# 2_Connection.net
KiCad netlist of a schematic drawn in Altium Designer
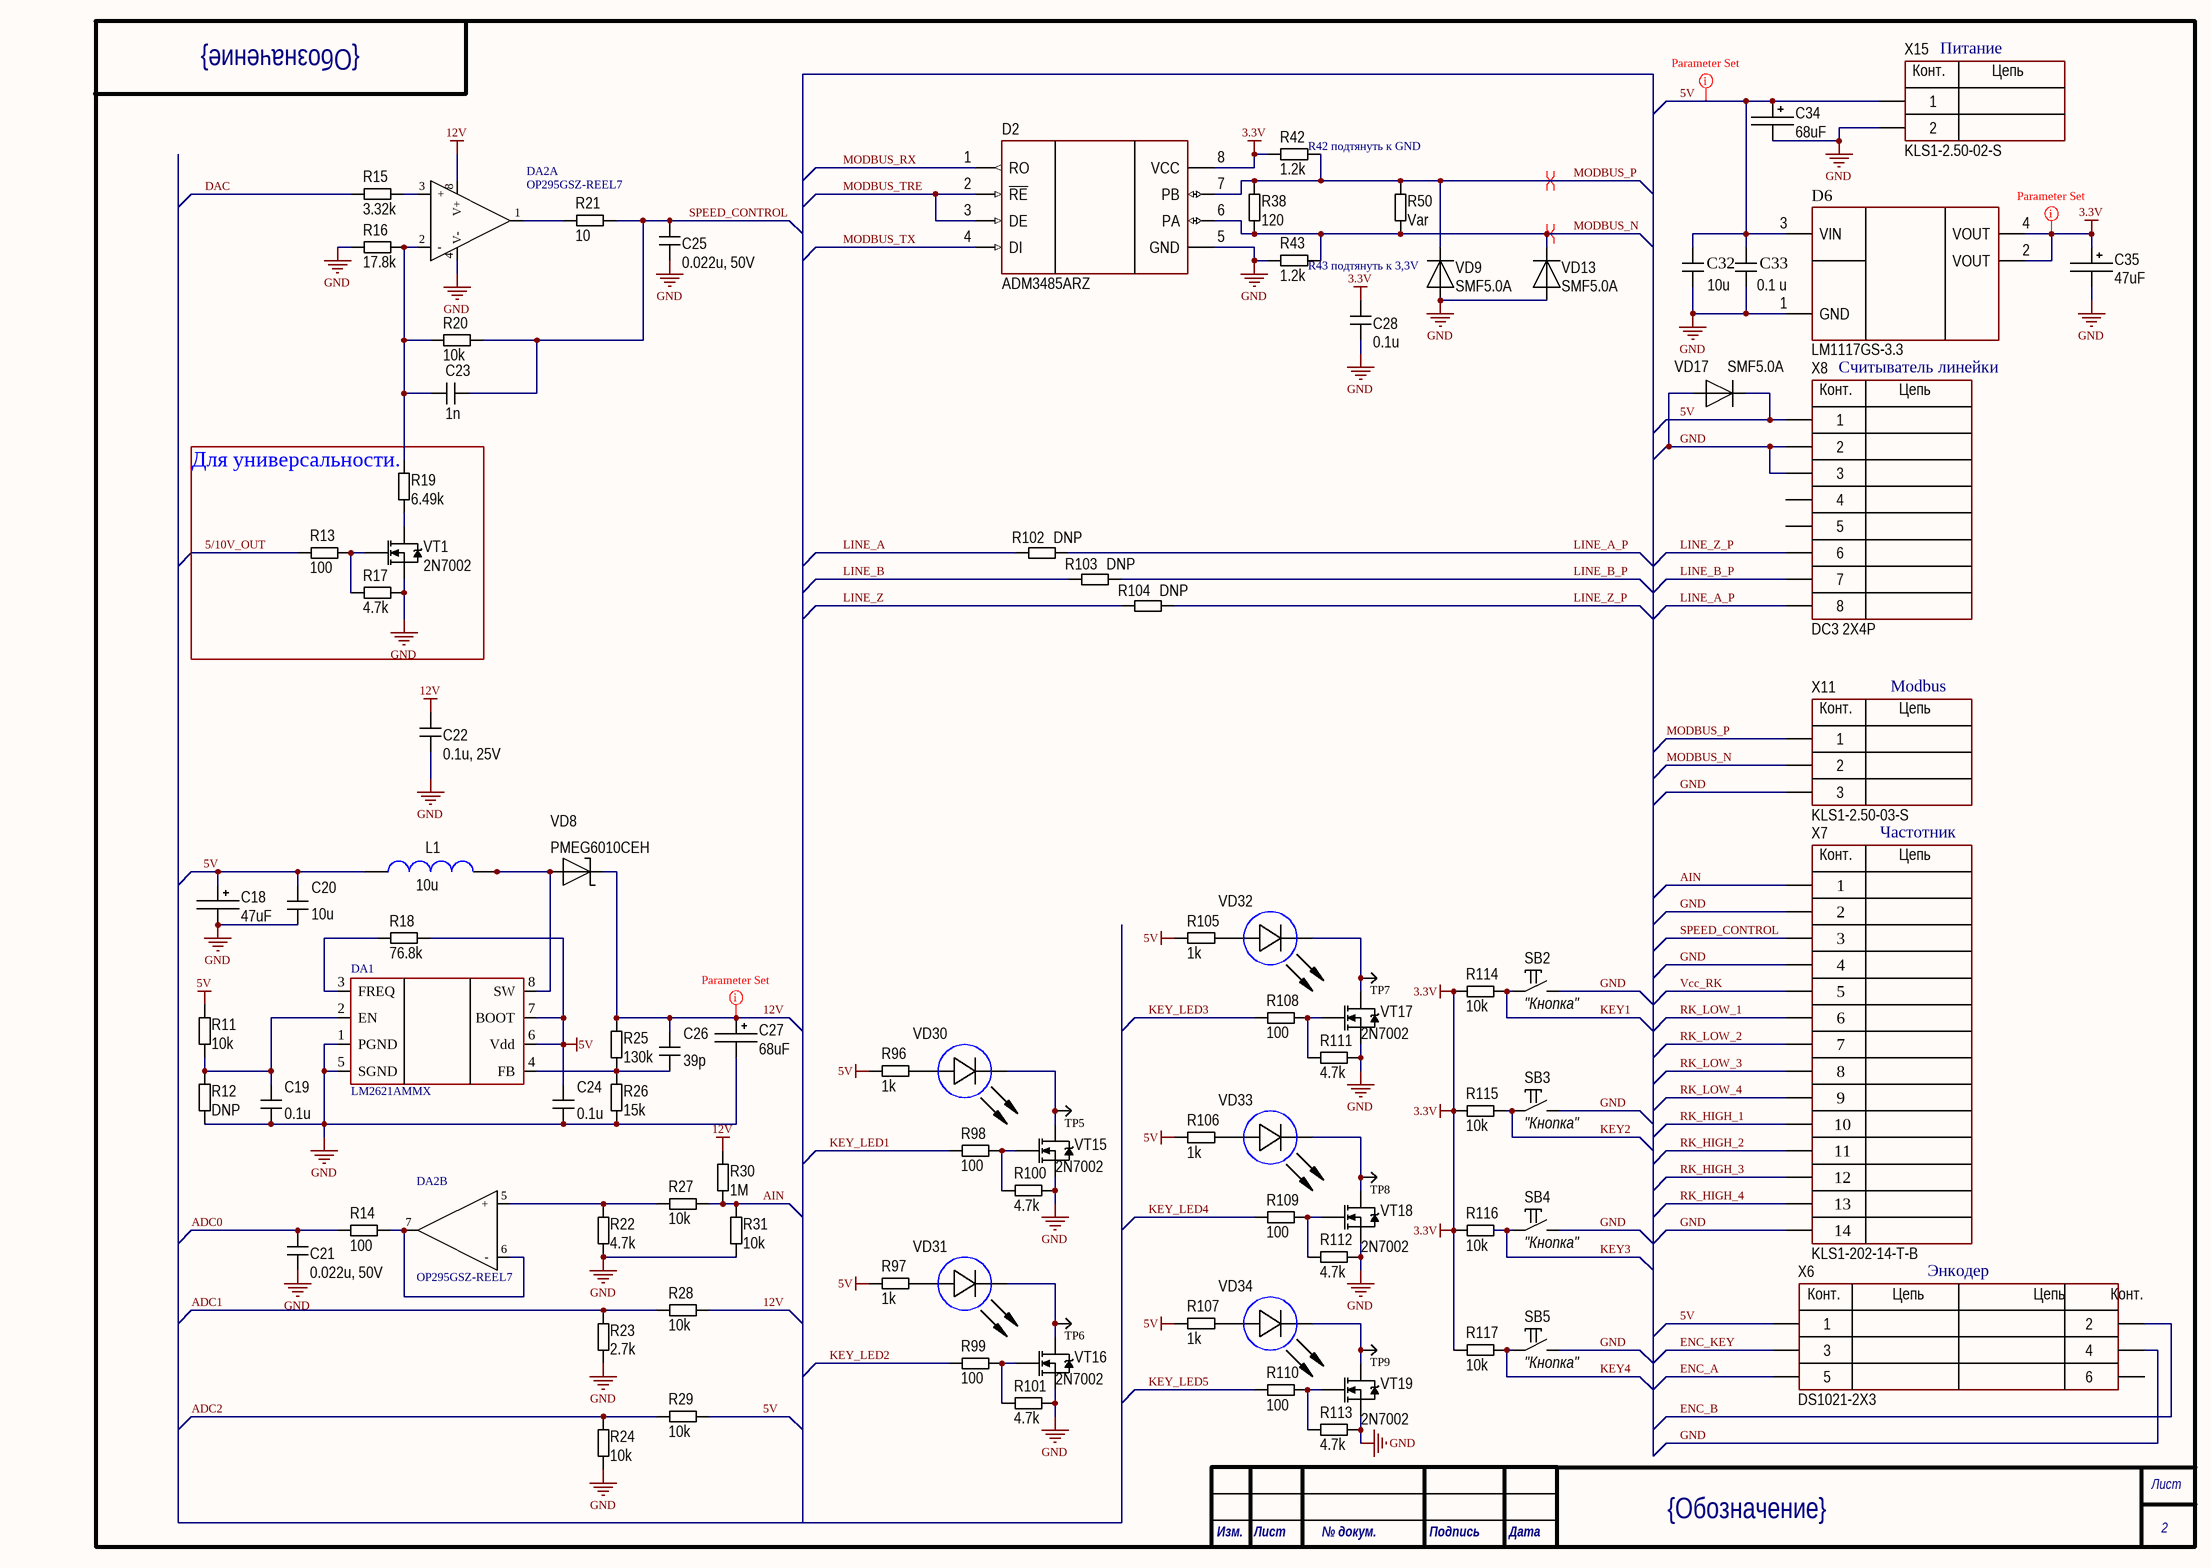
[diagram p0: 2_Connection.SchDoc]

(export (version "E")
  (design (tool "Eeschema 10.0.6"))
  (components
    (comp (ref "C18")
      (value "47uF")
      (footprint "TANTAL_B")
      (libsource (lib "Condensators") (part "TantalCap"))
    )
    (comp (ref "C19")
      (value "0.1u")
      (footprint "CH0603C")
      (libsource (lib "Condensators") (part "Capacitor"))
    )
    (comp (ref "C20") (value "10u") (footprint "CH0603C") (libsource (lib "Condensators") (part "Capacitor")))
    (comp (ref "C21")
      (value "0.022u, 50V")
      (footprint "CH0603C")
      (libsource (lib "Condensators") (part "Capacitor"))
    )
    (comp (ref "C22")
      (value "0.1u, 25V")
      (footprint "CH0603C")
      (libsource (lib "Condensators") (part "Capacitor"))
    )
    (comp (ref "C23") (value "1n") (footprint "CH0603C") (libsource (lib "Condensators") (part "Capacitor")))
    (comp (ref "C24")
      (value "0.1u")
      (footprint "CH0603C")
      (libsource (lib "Condensators") (part "Capacitor"))
    )
    (comp (ref "C25")
      (value "0.022u, 50V")
      (footprint "CH0603C")
      (libsource (lib "Condensators") (part "Capacitor"))
    )
    (comp (ref "C26") (value "39p") (footprint "CH0603C") (libsource (lib "Condensators") (part "Capacitor")))
    (comp (ref "C27")
      (value "68uF")
      (footprint "TANTAL_D")
      (libsource (lib "Condensators") (part "TantalCap"))
    )
    (comp (ref "C28")
      (value "0.1u")
      (footprint "CH0603C")
      (libsource (lib "Condensators") (part "Capacitor"))
    )
    (comp (ref "C32") (value "10u") (footprint "CH0805C") (libsource (lib "Condensators") (part "Capacitor")))
    (comp (ref "C33")
      (value "0.1 u")
      (footprint "CH0603C")
      (libsource (lib "Condensators") (part "Capacitor"))
    )
    (comp (ref "C34")
      (value "68uF")
      (footprint "TANTAL_B")
      (libsource (lib "Condensators") (part "TantalCap"))
    )
    (comp (ref "C35")
      (value "47uF")
      (footprint "TANTAL_A")
      (libsource (lib "Condensators") (part "TantalCap"))
    )
    (comp (ref "D2")
      (value "ADM3485ARZ")
      (footprint "8-SOIC")
      (description "RS485")
      (fields (field (name "MANUFACTURER") "Analog Devices Inc."))
      (libsource (lib "MicroIC") (part "ADM3485ARZ"))
    )
    (comp (ref "D6")
      (value "LM1117GS-3.3")
      (footprint "SOT223")
      (description "LDO")
      (fields (field (name "MANUFACTURER") "STMicroelectronics"))
      (libsource (lib "MicroIC") (part "LDL1117S33R"))
    )
    (comp (ref "DA1")
      (value "LM2621AMMX")
      (footprint "standard:8-SSOP")
      (libsource (lib "KSP_SchLib") (part "LM2623AMMX"))
    )
    (comp (ref "DA2")
      (value "OP295GSZ-REEL7")
      (footprint "standard:8-SOIC")
      (libsource (lib "KSP_SchLib") (part "OP295"))
    )
    (comp (ref "L1")
      (value "10u")
      (footprint "IND: IHLP2020")
      (libsource (lib "Inductance") (part "Inductor"))
    )
    (comp (ref "R11") (value "10k") (footprint "CH0603R") (libsource (lib "Resistors") (part "Resistor")))
    (comp (ref "R12") (value "DNP") (footprint "CH0603R") (libsource (lib "Resistors") (part "Resistor")))
    (comp (ref "R13") (value "100") (footprint "CH0603R") (libsource (lib "Resistors") (part "Resistor")))
    (comp (ref "R14") (value "100") (footprint "CH0603R") (libsource (lib "Resistors") (part "Resistor")))
    (comp (ref "R15") (value "3.32k") (footprint "CH0603R") (libsource (lib "Resistors") (part "Resistor")))
    (comp (ref "R16") (value "17.8k") (footprint "CH0603R") (libsource (lib "Resistors") (part "Resistor")))
    (comp (ref "R17") (value "4.7k") (footprint "CH0603R") (libsource (lib "Resistors") (part "Resistor")))
    (comp (ref "R18") (value "76.8k") (footprint "CH0603R") (libsource (lib "Resistors") (part "Resistor")))
    (comp (ref "R19") (value "6.49k") (footprint "CH0603R") (libsource (lib "Resistors") (part "Resistor")))
    (comp (ref "R20") (value "10k") (footprint "CH0603R") (libsource (lib "Resistors") (part "Resistor")))
    (comp (ref "R21") (value "10") (footprint "CH0603R") (libsource (lib "Resistors") (part "Resistor")))
    (comp (ref "R22") (value "4.7k") (footprint "CH0603R") (libsource (lib "Resistors") (part "Resistor")))
    (comp (ref "R23") (value "2.7k") (footprint "CH0603R") (libsource (lib "Resistors") (part "Resistor")))
    (comp (ref "R24") (value "10k") (footprint "CH0603R") (libsource (lib "Resistors") (part "Resistor")))
    (comp (ref "R25") (value "130k") (footprint "CH0603R") (libsource (lib "Resistors") (part "Resistor")))
    (comp (ref "R26") (value "15k") (footprint "CH0603R") (libsource (lib "Resistors") (part "Resistor")))
    (comp (ref "R27") (value "10k") (footprint "CH0603R") (libsource (lib "Resistors") (part "Resistor")))
    (comp (ref "R28") (value "10k") (footprint "CH0603R") (libsource (lib "Resistors") (part "Resistor")))
    (comp (ref "R29") (value "10k") (footprint "CH0603R") (libsource (lib "Resistors") (part "Resistor")))
    (comp (ref "R30") (value "1M") (footprint "CH0603R") (libsource (lib "Resistors") (part "Resistor")))
    (comp (ref "R31") (value "10k") (footprint "CH0603R") (libsource (lib "Resistors") (part "Resistor")))
    (comp (ref "R38") (value "120") (footprint "CH1206R") (libsource (lib "Resistors") (part "Resistor")))
    (comp (ref "R42") (value "1.2k") (footprint "CH0603R") (libsource (lib "Resistors") (part "Resistor")))
    (comp (ref "R43") (value "1.2k") (footprint "CH0603R") (libsource (lib "Resistors") (part "Resistor")))
    (comp (ref "R50")
      (value "Var")
      (footprint "CH1206R")
      (fields (field (name "PART") "JMV0805S5R6T661"))
      (libsource (lib "Resistors") (part "Resistor"))
    )
    (comp (ref "R96") (value "1k") (footprint "CH0805R") (libsource (lib "Resistors") (part "Resistor")))
    (comp (ref "R97") (value "1k") (footprint "CH0805R") (libsource (lib "Resistors") (part "Resistor")))
    (comp (ref "R98") (value "100") (footprint "CH0603R") (libsource (lib "Resistors") (part "Resistor")))
    (comp (ref "R99") (value "100") (footprint "CH0603R") (libsource (lib "Resistors") (part "Resistor")))
    (comp (ref "R100") (value "4.7k") (footprint "CH0603R") (libsource (lib "Resistors") (part "Resistor")))
    (comp (ref "R101") (value "4.7k") (footprint "CH0603R") (libsource (lib "Resistors") (part "Resistor")))
    (comp (ref "R102") (value "DNP") (footprint "CH0603R") (libsource (lib "Resistors") (part "Resistor")))
    (comp (ref "R103") (value "DNP") (footprint "CH0603R") (libsource (lib "Resistors") (part "Resistor")))
    (comp (ref "R104") (value "DNP") (footprint "CH0603R") (libsource (lib "Resistors") (part "Resistor")))
    (comp (ref "R105") (value "1k") (footprint "CH0805R") (libsource (lib "Resistors") (part "Resistor")))
    (comp (ref "R106") (value "1k") (footprint "CH0805R") (libsource (lib "Resistors") (part "Resistor")))
    (comp (ref "R107") (value "1k") (footprint "CH0805R") (libsource (lib "Resistors") (part "Resistor")))
    (comp (ref "R108") (value "100") (footprint "CH0603R") (libsource (lib "Resistors") (part "Resistor")))
    (comp (ref "R109") (value "100") (footprint "CH0603R") (libsource (lib "Resistors") (part "Resistor")))
    (comp (ref "R110") (value "100") (footprint "CH0603R") (libsource (lib "Resistors") (part "Resistor")))
    (comp (ref "R111") (value "4.7k") (footprint "CH0603R") (libsource (lib "Resistors") (part "Resistor")))
    (comp (ref "R112") (value "4.7k") (footprint "CH0603R") (libsource (lib "Resistors") (part "Resistor")))
    (comp (ref "R113") (value "4.7k") (footprint "CH0603R") (libsource (lib "Resistors") (part "Resistor")))
    (comp (ref "R114") (value "10k") (footprint "CH0603R") (libsource (lib "Resistors") (part "Resistor")))
    (comp (ref "R115") (value "10k") (footprint "CH0603R") (libsource (lib "Resistors") (part "Resistor")))
    (comp (ref "R116") (value "10k") (footprint "CH0603R") (libsource (lib "Resistors") (part "Resistor")))
    (comp (ref "R117") (value "10k") (footprint "CH0603R") (libsource (lib "Resistors") (part "Resistor")))
    (comp (ref "SB2")
      (value "\"Кнопка\"")
      (footprint "BUT: SKQGADE010")
      (description "6x6 mm")
      (libsource (lib "Connectors") (part "Tactile switches"))
    )
    (comp (ref "SB3")
      (value "\"Кнопка\"")
      (footprint "BUT: SKQGADE010")
      (description "6x6 mm")
      (libsource (lib "Connectors") (part "Tactile switches"))
    )
    (comp (ref "SB4")
      (value "\"Кнопка\"")
      (footprint "BUT: SKQGADE010")
      (description "6x6 mm")
      (libsource (lib "Connectors") (part "Tactile switches"))
    )
    (comp (ref "SB5")
      (value "\"Кнопка\"")
      (footprint "BUT: SKQGADE010")
      (description "6x6 mm")
      (libsource (lib "Connectors") (part "Tactile switches"))
    )
    (comp (ref "TP5") (value "~") (footprint "TestPoint") (libsource (lib "Melochi") (part "TestPoint")))
    (comp (ref "TP6") (value "~") (footprint "TestPoint") (libsource (lib "Melochi") (part "TestPoint")))
    (comp (ref "TP7") (value "~") (footprint "TestPoint") (libsource (lib "Melochi") (part "TestPoint")))
    (comp (ref "TP8") (value "~") (footprint "TestPoint") (libsource (lib "Melochi") (part "TestPoint")))
    (comp (ref "TP9") (value "~") (footprint "TestPoint") (libsource (lib "Melochi") (part "TestPoint")))
    (comp (ref "VD8")
      (value "PMEG6010CEH")
      (footprint "SOD123F")
      (libsource (lib "Diods") (part "Diod Schottky"))
    )
    (comp (ref "VD9")
      (value "SMF5.0A")
      (footprint "SOD123F")
      (fields (field (name "PART NUM") "SMAF5.0A"))
      (libsource (lib "Diods") (part "Diod"))
    )
    (comp (ref "VD13")
      (value "SMF5.0A")
      (footprint "SOD123F")
      (fields (field (name "PART NUM") "SMAF5.0A"))
      (libsource (lib "Diods") (part "Diod"))
    )
    (comp (ref "VD17")
      (value "SMF5.0A")
      (footprint "SOD123F")
      (fields (field (name "PART NUM") "SMAF5.0A"))
      (libsource (lib "Diods") (part "Diod"))
    )
    (comp (ref "VD30") (value "BLUE") (footprint "CH0603LB") (libsource (lib "Diods") (part "LED_1")))
    (comp (ref "VD31") (value "BLUE") (footprint "CH0603LB") (libsource (lib "Diods") (part "LED_1")))
    (comp (ref "VD32") (value "BLUE") (footprint "CH0603LB") (libsource (lib "Diods") (part "LED_1")))
    (comp (ref "VD33") (value "BLUE") (footprint "CH0603LB") (libsource (lib "Diods") (part "LED_1")))
    (comp (ref "VD34") (value "BLUE") (footprint "CH0603LB") (libsource (lib "Diods") (part "LED_1")))
    (comp (ref "VT1")
      (value "2N7002")
      (footprint "SOT23_123")
      (description "Mosfet")
      (libsource (lib "Tranzistor") (part "N-chanel"))
    )
    (comp (ref "VT15")
      (value "2N7002")
      (footprint "SOT23_123")
      (description "Mosfet")
      (libsource (lib "Tranzistor") (part "N-chanel"))
    )
    (comp (ref "VT16")
      (value "2N7002")
      (footprint "SOT23_123")
      (description "Mosfet")
      (libsource (lib "Tranzistor") (part "N-chanel"))
    )
    (comp (ref "VT17")
      (value "2N7002")
      (footprint "SOT23_123")
      (description "Mosfet")
      (libsource (lib "Tranzistor") (part "N-chanel"))
    )
    (comp (ref "VT18")
      (value "2N7002")
      (footprint "SOT23_123")
      (description "Mosfet")
      (libsource (lib "Tranzistor") (part "N-chanel"))
    )
    (comp (ref "VT19")
      (value "2N7002")
      (footprint "SOT23_123")
      (description "Mosfet")
      (libsource (lib "Tranzistor") (part "N-chanel"))
    )
    (comp (ref "X6")
      (value "DS1021-2X3")
      (footprint "CON: PLD-6 (without body)")
      (libsource (lib "Connectors") (part "6(2)-Connector"))
    )
    (comp (ref "X7")
      (value "KLS1-202-14-T-B")
      (footprint "CON: IDC-14MS")
      (libsource (lib "Connectors") (part "14-Connector"))
    )
    (comp (ref "X8")
      (value "DC3 2X4P")
      (footprint "CON: DC3 2x4P")
      (libsource (lib "Connectors") (part "8-Connector"))
    )
    (comp (ref "X11")
      (value "KLS1-2.50-03-S")
      (footprint "CON: CWF-3")
      (libsource (lib "Connectors") (part "3-Connector"))
    )
    (comp (ref "X15")
      (value "KLS1-2.50-02-S")
      (footprint "CON: CWF-2")
      (libsource (lib "Connectors") (part "2-Connector"))
    )
  )
  (nets
    (net (code "1") (name "/5{slash}10V_OUT") (class "Default")
      (node (ref "R13") (pin "2") (pinfunction "2_2") (pintype "passive"))
    )
    (net (code "2") (name "/ADC0") (class "Default")
      (node (ref "C21") (pin "2") (pinfunction "2_2") (pintype "passive"))
      (node (ref "R14") (pin "1") (pinfunction "1_1") (pintype "passive"))
    )
    (net (code "3") (name "/ADC1") (class "Default")
      (node (ref "R23") (pin "1") (pinfunction "1_1") (pintype "passive"))
      (node (ref "R28") (pin "2") (pinfunction "2_2") (pintype "passive"))
    )
    (net (code "4") (name "/ADC2") (class "Default")
      (node (ref "R24") (pin "1") (pinfunction "1_1") (pintype "passive"))
      (node (ref "R29") (pin "2") (pinfunction "2_2") (pintype "passive"))
    )
    (net (code "5") (name "/AIN") (class "Default")
      (node (ref "R27") (pin "1") (pinfunction "1_1") (pintype "passive"))
      (node (ref "R30") (pin "2") (pinfunction "2_2") (pintype "passive"))
      (node (ref "R31") (pin "1") (pinfunction "1_1") (pintype "passive"))
      (node (ref "X7") (pin "1") (pinfunction "1_1") (pintype "passive"))
    )
    (net (code "6") (name "/DAC") (class "Default")
      (node (ref "R15") (pin "2") (pinfunction "2_2") (pintype "passive"))
    )
    (net (code "7") (name "/ENC_A") (class "Default")
      (node (ref "X6") (pin "5") (pinfunction "5_5") (pintype "passive"))
    )
    (net (code "8") (name "/ENC_B") (class "Default")
      (node (ref "X6") (pin "2") (pinfunction "2_2") (pintype "passive"))
    )
    (net (code "9") (name "/ENC_KEY") (class "Default")
      (node (ref "X6") (pin "3") (pinfunction "3_3") (pintype "passive"))
    )
    (net (code "10") (name "/KEY1") (class "Default")
      (node (ref "R114") (pin "1") (pinfunction "1_1") (pintype "passive"))
      (node (ref "SB2") (pin "1") (pinfunction "1_1") (pintype "passive"))
    )
    (net (code "11") (name "/KEY2") (class "Default")
      (node (ref "R115") (pin "1") (pinfunction "1_1") (pintype "passive"))
      (node (ref "SB3") (pin "1") (pinfunction "1_1") (pintype "passive"))
    )
    (net (code "12") (name "/KEY3") (class "Default")
      (node (ref "R116") (pin "1") (pinfunction "1_1") (pintype "passive"))
      (node (ref "SB4") (pin "1") (pinfunction "1_1") (pintype "passive"))
    )
    (net (code "13") (name "/KEY4") (class "Default")
      (node (ref "R117") (pin "1") (pinfunction "1_1") (pintype "passive"))
      (node (ref "SB5") (pin "1") (pinfunction "1_1") (pintype "passive"))
    )
    (net (code "14") (name "/KEY_LED1") (class "Default")
      (node (ref "R98") (pin "2") (pinfunction "2_2") (pintype "passive"))
    )
    (net (code "15") (name "/KEY_LED2") (class "Default")
      (node (ref "R99") (pin "2") (pinfunction "2_2") (pintype "passive"))
    )
    (net (code "16") (name "/KEY_LED3") (class "Default")
      (node (ref "R108") (pin "2") (pinfunction "2_2") (pintype "passive"))
    )
    (net (code "17") (name "/KEY_LED4") (class "Default")
      (node (ref "R109") (pin "2") (pinfunction "2_2") (pintype "passive"))
    )
    (net (code "18") (name "/KEY_LED5") (class "Default")
      (node (ref "R110") (pin "2") (pinfunction "2_2") (pintype "passive"))
    )
    (net (code "19") (name "/LINE_A") (class "Default")
      (node (ref "R102") (pin "2") (pinfunction "2_2") (pintype "passive"))
    )
    (net (code "20") (name "/LINE_A_P") (class "Default")
      (node (ref "R102") (pin "1") (pinfunction "1_1") (pintype "passive"))
      (node (ref "X8") (pin "8") (pinfunction "8_8") (pintype "power_in"))
    )
    (net (code "21") (name "/LINE_B") (class "Default")
      (node (ref "R103") (pin "2") (pinfunction "2_2") (pintype "passive"))
    )
    (net (code "22") (name "/LINE_B_P") (class "Default")
      (node (ref "R103") (pin "1") (pinfunction "1_1") (pintype "passive"))
      (node (ref "X8") (pin "7") (pinfunction "7_7") (pintype "power_in"))
    )
    (net (code "23") (name "/LINE_Z") (class "Default")
      (node (ref "R104") (pin "2") (pinfunction "2_2") (pintype "passive"))
    )
    (net (code "24") (name "/LINE_Z_P") (class "Default")
      (node (ref "R104") (pin "1") (pinfunction "1_1") (pintype "passive"))
      (node (ref "X8") (pin "6") (pinfunction "6_6") (pintype "power_in"))
    )
    (net (code "25") (name "/MODBUS_N") (class "Default")
      (node (ref "D2") (pin "6") (pinfunction "PA_6") (pintype "bidirectional"))
      (node (ref "R38") (pin "1") (pinfunction "1_1") (pintype "passive"))
      (node (ref "R43") (pin "1") (pinfunction "1_1") (pintype "passive"))
      (node (ref "R50") (pin "1") (pinfunction "1_1") (pintype "passive"))
      (node (ref "VD13") (pin "2") (pinfunction "2_2") (pintype "passive"))
      (node (ref "X11") (pin "2") (pinfunction "2_2") (pintype "passive"))
    )
    (net (code "26") (name "/MODBUS_P") (class "Default")
      (node (ref "D2") (pin "7") (pinfunction "PB_7") (pintype "bidirectional"))
      (node (ref "R38") (pin "2") (pinfunction "2_2") (pintype "passive"))
      (node (ref "R42") (pin "1") (pinfunction "1_1") (pintype "passive"))
      (node (ref "R50") (pin "2") (pinfunction "2_2") (pintype "passive"))
      (node (ref "VD9") (pin "2") (pinfunction "2_2") (pintype "passive"))
      (node (ref "X11") (pin "1") (pinfunction "1_1") (pintype "passive"))
    )
    (net (code "27") (name "/MODBUS_RX") (class "Default")
      (node (ref "D2") (pin "1") (pinfunction "RO_1") (pintype "output"))
    )
    (net (code "28") (name "/MODBUS_TRE") (class "Default")
      (node (ref "D2") (pin "2") (pinfunction "~{RE}_2") (pintype "input"))
      (node (ref "D2") (pin "3") (pinfunction "DE_3") (pintype "input"))
    )
    (net (code "29") (name "/MODBUS_TX") (class "Default")
      (node (ref "D2") (pin "4") (pinfunction "DI_4") (pintype "input"))
    )
    (net (code "30") (name "/RK_HIGH_1") (class "Default")
      (node (ref "X7") (pin "10") (pinfunction "10_10") (pintype "power_in"))
    )
    (net (code "31") (name "/RK_HIGH_2") (class "Default")
      (node (ref "X7") (pin "11") (pinfunction "11_11") (pintype "power_in"))
    )
    (net (code "32") (name "/RK_HIGH_3") (class "Default")
      (node (ref "X7") (pin "12") (pinfunction "12_12") (pintype "power_in"))
    )
    (net (code "33") (name "/RK_HIGH_4") (class "Default")
      (node (ref "X7") (pin "13") (pinfunction "13_13") (pintype "power_in"))
    )
    (net (code "34") (name "/RK_LOW_1") (class "Default")
      (node (ref "X7") (pin "6") (pinfunction "6_6") (pintype "power_in"))
    )
    (net (code "35") (name "/RK_LOW_2") (class "Default")
      (node (ref "X7") (pin "7") (pinfunction "7_7") (pintype "power_in"))
    )
    (net (code "36") (name "/RK_LOW_3") (class "Default")
      (node (ref "X7") (pin "8") (pinfunction "8_8") (pintype "power_in"))
    )
    (net (code "37") (name "/RK_LOW_4") (class "Default")
      (node (ref "X7") (pin "9") (pinfunction "9_9") (pintype "power_in"))
    )
    (net (code "38") (name "/SPEED_CONTROL") (class "Default")
      (node (ref "C23") (pin "1") (pinfunction "1_1") (pintype "passive"))
      (node (ref "C25") (pin "2") (pinfunction "2_2") (pintype "passive"))
      (node (ref "R20") (pin "1") (pinfunction "1_1") (pintype "passive"))
      (node (ref "R21") (pin "1") (pinfunction "1_1") (pintype "passive"))
      (node (ref "X7") (pin "3") (pinfunction "3_3") (pintype "power_in"))
    )
    (net (code "39") (name "/Vcc_RK") (class "Default")
      (node (ref "X7") (pin "5") (pinfunction "5_5") (pintype "power_in"))
    )
    (net (code "40") (name "3.3V") (class "Default")
      (node (ref "C28") (pin "2") (pinfunction "2_2") (pintype "passive"))
      (node (ref "C35") (pin "1") (pinfunction "1_1") (pintype "power_in"))
      (node (ref "D2") (pin "8") (pinfunction "VCC_8") (pintype "power_in"))
      (node (ref "D6") (pin "2") (pinfunction "VOUT_2") (pintype "power_in"))
      (node (ref "D6") (pin "4") (pinfunction "VOUT_4") (pintype "power_in"))
      (node (ref "R114") (pin "2") (pinfunction "2_2") (pintype "passive"))
      (node (ref "R115") (pin "2") (pinfunction "2_2") (pintype "passive"))
      (node (ref "R116") (pin "2") (pinfunction "2_2") (pintype "passive"))
      (node (ref "R117") (pin "2") (pinfunction "2_2") (pintype "passive"))
      (node (ref "R42") (pin "2") (pinfunction "2_2") (pintype "passive"))
    )
    (net (code "41") (name "5V") (class "Default")
      (node (ref "C18") (pin "1") (pinfunction "1_1") (pintype "power_in"))
      (node (ref "C20") (pin "2") (pinfunction "2_2") (pintype "passive"))
      (node (ref "C24") (pin "2") (pinfunction "2_2") (pintype "passive"))
      (node (ref "C32") (pin "2") (pinfunction "2_2") (pintype "passive"))
      (node (ref "C33") (pin "2") (pinfunction "2_2") (pintype "passive"))
      (node (ref "C34") (pin "1") (pinfunction "1_1") (pintype "power_in"))
      (node (ref "D6") (pin "3") (pinfunction "VIN_3") (pintype "power_in"))
      (node (ref "DA1") (pin "6") (pinfunction "Vdd_6") (pintype "passive"))
      (node (ref "DA1") (pin "7") (pinfunction "BOOT_7") (pintype "passive"))
      (node (ref "L1") (pin "2") (pinfunction "2_2") (pintype "passive"))
      (node (ref "R105") (pin "2") (pinfunction "2_2") (pintype "passive"))
      (node (ref "R106") (pin "2") (pinfunction "2_2") (pintype "passive"))
      (node (ref "R107") (pin "2") (pinfunction "2_2") (pintype "passive"))
      (node (ref "R11") (pin "1") (pinfunction "1_1") (pintype "passive"))
      (node (ref "R18") (pin "1") (pinfunction "1_1") (pintype "passive"))
      (node (ref "R29") (pin "1") (pinfunction "1_1") (pintype "passive"))
      (node (ref "R96") (pin "2") (pinfunction "2_2") (pintype "passive"))
      (node (ref "R97") (pin "2") (pinfunction "2_2") (pintype "passive"))
      (node (ref "VD17") (pin "2") (pinfunction "2_2") (pintype "passive"))
      (node (ref "X15") (pin "1") (pinfunction "1_1") (pintype "passive"))
      (node (ref "X6") (pin "1") (pinfunction "1_1") (pintype "passive"))
      (node (ref "X8") (pin "1") (pinfunction "1_1") (pintype "passive"))
    )
    (net (code "42") (name "12V") (class "Default")
      (node (ref "C22") (pin "2") (pinfunction "2_2") (pintype "passive"))
      (node (ref "C26") (pin "2") (pinfunction "2_2") (pintype "passive"))
      (node (ref "C27") (pin "1") (pinfunction "1_1") (pintype "power_in"))
      (node (ref "DA2") (pin "8") (pinfunction "V+_8") (pintype "passive"))
      (node (ref "R25") (pin "1") (pinfunction "1_1") (pintype "passive"))
      (node (ref "R28") (pin "1") (pinfunction "1_1") (pintype "passive"))
      (node (ref "R30") (pin "1") (pinfunction "1_1") (pintype "passive"))
      (node (ref "VD8") (pin "2") (pinfunction "2_2") (pintype "passive"))
    )
    (net (code "43") (name "GND") (class "Default")
      (node (ref "C18") (pin "2") (pinfunction "2_2") (pintype "power_in"))
      (node (ref "C19") (pin "1") (pinfunction "1_1") (pintype "passive"))
      (node (ref "C20") (pin "1") (pinfunction "1_1") (pintype "passive"))
      (node (ref "C21") (pin "1") (pinfunction "1_1") (pintype "passive"))
      (node (ref "C22") (pin "1") (pinfunction "1_1") (pintype "passive"))
      (node (ref "C24") (pin "1") (pinfunction "1_1") (pintype "passive"))
      (node (ref "C25") (pin "1") (pinfunction "1_1") (pintype "passive"))
      (node (ref "C27") (pin "2") (pinfunction "2_2") (pintype "power_in"))
      (node (ref "C28") (pin "1") (pinfunction "1_1") (pintype "passive"))
      (node (ref "C32") (pin "1") (pinfunction "1_1") (pintype "passive"))
      (node (ref "C33") (pin "1") (pinfunction "1_1") (pintype "passive"))
      (node (ref "C34") (pin "2") (pinfunction "2_2") (pintype "power_in"))
      (node (ref "C35") (pin "2") (pinfunction "2_2") (pintype "power_in"))
      (node (ref "D2") (pin "5") (pinfunction "GND_5") (pintype "power_in"))
      (node (ref "D6") (pin "1") (pinfunction "GND_1") (pintype "power_in"))
      (node (ref "DA1") (pin "1") (pinfunction "PGND_1") (pintype "passive"))
      (node (ref "DA1") (pin "5") (pinfunction "SGND_5") (pintype "passive"))
      (node (ref "DA2") (pin "4") (pinfunction "V-_4") (pintype "passive"))
      (node (ref "R100") (pin "1") (pinfunction "1_1") (pintype "passive"))
      (node (ref "R101") (pin "1") (pinfunction "1_1") (pintype "passive"))
      (node (ref "R111") (pin "1") (pinfunction "1_1") (pintype "passive"))
      (node (ref "R112") (pin "1") (pinfunction "1_1") (pintype "passive"))
      (node (ref "R113") (pin "1") (pinfunction "1_1") (pintype "passive"))
      (node (ref "R12") (pin "2") (pinfunction "2_2") (pintype "passive"))
      (node (ref "R16") (pin "2") (pinfunction "2_2") (pintype "passive"))
      (node (ref "R17") (pin "1") (pinfunction "1_1") (pintype "passive"))
      (node (ref "R22") (pin "2") (pinfunction "2_2") (pintype "passive"))
      (node (ref "R23") (pin "2") (pinfunction "2_2") (pintype "passive"))
      (node (ref "R24") (pin "2") (pinfunction "2_2") (pintype "passive"))
      (node (ref "R26") (pin "2") (pinfunction "2_2") (pintype "passive"))
      (node (ref "R31") (pin "2") (pinfunction "2_2") (pintype "passive"))
      (node (ref "R43") (pin "2") (pinfunction "2_2") (pintype "passive"))
      (node (ref "SB2") (pin "2") (pinfunction "2_2") (pintype "passive"))
      (node (ref "SB3") (pin "2") (pinfunction "2_2") (pintype "passive"))
      (node (ref "SB4") (pin "2") (pinfunction "2_2") (pintype "passive"))
      (node (ref "SB5") (pin "2") (pinfunction "2_2") (pintype "passive"))
      (node (ref "VD13") (pin "1") (pinfunction "1_1") (pintype "passive"))
      (node (ref "VD17") (pin "1") (pinfunction "1_1") (pintype "passive"))
      (node (ref "VD9") (pin "1") (pinfunction "1_1") (pintype "passive"))
      (node (ref "VT1") (pin "3") (pinfunction "S_3") (pintype "passive"))
      (node (ref "VT15") (pin "3") (pinfunction "S_3") (pintype "passive"))
      (node (ref "VT16") (pin "3") (pinfunction "S_3") (pintype "passive"))
      (node (ref "VT17") (pin "3") (pinfunction "S_3") (pintype "passive"))
      (node (ref "VT18") (pin "3") (pinfunction "S_3") (pintype "passive"))
      (node (ref "VT19") (pin "3") (pinfunction "S_3") (pintype "passive"))
      (node (ref "X11") (pin "3") (pinfunction "3_3") (pintype "power_in"))
      (node (ref "X15") (pin "2") (pinfunction "2_2") (pintype "passive"))
      (node (ref "X6") (pin "4") (pinfunction "4_4") (pintype "passive"))
      (node (ref "X7") (pin "14") (pinfunction "14_14") (pintype "power_in"))
      (node (ref "X7") (pin "2") (pinfunction "2_2") (pintype "passive"))
      (node (ref "X7") (pin "4") (pinfunction "4_4") (pintype "power_in"))
      (node (ref "X8") (pin "2") (pinfunction "2_2") (pintype "passive"))
      (node (ref "X8") (pin "3") (pinfunction "3_3") (pintype "power_in"))
    )
    (net (code "44") (name "Net-(DA1-EN)") (class "Default")
      (node (ref "C19") (pin "2") (pinfunction "2_2") (pintype "passive"))
      (node (ref "DA1") (pin "2") (pinfunction "EN_2") (pintype "passive"))
      (node (ref "R11") (pin "2") (pinfunction "2_2") (pintype "passive"))
      (node (ref "R12") (pin "1") (pinfunction "1_1") (pintype "passive"))
    )
    (net (code "45") (name "Net-(DA1-FB)") (class "Default")
      (node (ref "C26") (pin "1") (pinfunction "1_1") (pintype "passive"))
      (node (ref "DA1") (pin "4") (pinfunction "FB_4") (pintype "passive"))
      (node (ref "R25") (pin "2") (pinfunction "2_2") (pintype "passive"))
      (node (ref "R26") (pin "1") (pinfunction "1_1") (pintype "passive"))
    )
    (net (code "46") (name "Net-(DA1-FREQ)") (class "Default")
      (node (ref "DA1") (pin "3") (pinfunction "FREQ_3") (pintype "passive"))
      (node (ref "R18") (pin "2") (pinfunction "2_2") (pintype "passive"))
    )
    (net (code "47") (name "Net-(DA1-SW)") (class "Default")
      (node (ref "DA1") (pin "8") (pinfunction "SW_8") (pintype "passive"))
      (node (ref "L1") (pin "1") (pinfunction "1_1") (pintype "passive"))
      (node (ref "VD8") (pin "1") (pinfunction "1_1") (pintype "passive"))
    )
    (net (code "48") (name "Net-(DA2A-+)") (class "Default")
      (node (ref "DA2") (pin "3") (pinfunction "+_3") (pintype "passive"))
      (node (ref "R15") (pin "1") (pinfunction "1_1") (pintype "passive"))
    )
    (net (code "49") (name "Net-(DA2A--)") (class "Default")
      (node (ref "C23") (pin "2") (pinfunction "2_2") (pintype "passive"))
      (node (ref "DA2") (pin "2") (pinfunction "-_2") (pintype "passive"))
      (node (ref "R16") (pin "1") (pinfunction "1_1") (pintype "passive"))
      (node (ref "R19") (pin "1") (pinfunction "1_1") (pintype "passive"))
      (node (ref "R20") (pin "2") (pinfunction "2_2") (pintype "passive"))
    )
    (net (code "50") (name "Net-(DA2A-OUT)") (class "Default")
      (node (ref "DA2") (pin "1") (pinfunction "OUT_1") (pintype "passive"))
      (node (ref "R21") (pin "2") (pinfunction "2_2") (pintype "passive"))
    )
    (net (code "51") (name "Net-(DA2B-+)") (class "Default")
      (node (ref "DA2") (pin "5") (pinfunction "+_5") (pintype "passive"))
      (node (ref "R22") (pin "1") (pinfunction "1_1") (pintype "passive"))
      (node (ref "R27") (pin "2") (pinfunction "2_2") (pintype "passive"))
    )
    (net (code "52") (name "Net-(DA2B--)") (class "Default")
      (node (ref "DA2") (pin "6") (pinfunction "-_6") (pintype "passive"))
      (node (ref "DA2") (pin "7") (pinfunction "OUT_7") (pintype "passive"))
      (node (ref "R14") (pin "2") (pinfunction "2_2") (pintype "passive"))
    )
    (net (code "53") (name "Net-(VD30-A)") (class "Default")
      (node (ref "R96") (pin "1") (pinfunction "1_1") (pintype "passive"))
      (node (ref "VD30") (pin "1") (pinfunction "A_1") (pintype "passive"))
    )
    (net (code "54") (name "Net-(VD30-C)") (class "Default")
      (node (ref "TP5") (pin "0") (pinfunction "0_0") (pintype "passive"))
      (node (ref "VD30") (pin "2") (pinfunction "C_2") (pintype "passive"))
      (node (ref "VT15") (pin "2") (pinfunction "D_2") (pintype "passive"))
    )
    (net (code "55") (name "Net-(VD31-A)") (class "Default")
      (node (ref "R97") (pin "1") (pinfunction "1_1") (pintype "passive"))
      (node (ref "VD31") (pin "1") (pinfunction "A_1") (pintype "passive"))
    )
    (net (code "56") (name "Net-(VD31-C)") (class "Default")
      (node (ref "TP6") (pin "0") (pinfunction "0_0") (pintype "passive"))
      (node (ref "VD31") (pin "2") (pinfunction "C_2") (pintype "passive"))
      (node (ref "VT16") (pin "2") (pinfunction "D_2") (pintype "passive"))
    )
    (net (code "57") (name "Net-(VD32-A)") (class "Default")
      (node (ref "R105") (pin "1") (pinfunction "1_1") (pintype "passive"))
      (node (ref "VD32") (pin "1") (pinfunction "A_1") (pintype "passive"))
    )
    (net (code "58") (name "Net-(VD32-C)") (class "Default")
      (node (ref "TP7") (pin "0") (pinfunction "0_0") (pintype "passive"))
      (node (ref "VD32") (pin "2") (pinfunction "C_2") (pintype "passive"))
      (node (ref "VT17") (pin "2") (pinfunction "D_2") (pintype "passive"))
    )
    (net (code "59") (name "Net-(VD33-A)") (class "Default")
      (node (ref "R106") (pin "1") (pinfunction "1_1") (pintype "passive"))
      (node (ref "VD33") (pin "1") (pinfunction "A_1") (pintype "passive"))
    )
    (net (code "60") (name "Net-(VD33-C)") (class "Default")
      (node (ref "TP8") (pin "0") (pinfunction "0_0") (pintype "passive"))
      (node (ref "VD33") (pin "2") (pinfunction "C_2") (pintype "passive"))
      (node (ref "VT18") (pin "2") (pinfunction "D_2") (pintype "passive"))
    )
    (net (code "61") (name "Net-(VD34-A)") (class "Default")
      (node (ref "R107") (pin "1") (pinfunction "1_1") (pintype "passive"))
      (node (ref "VD34") (pin "1") (pinfunction "A_1") (pintype "passive"))
    )
    (net (code "62") (name "Net-(VD34-C)") (class "Default")
      (node (ref "TP9") (pin "0") (pinfunction "0_0") (pintype "passive"))
      (node (ref "VD34") (pin "2") (pinfunction "C_2") (pintype "passive"))
      (node (ref "VT19") (pin "2") (pinfunction "D_2") (pintype "passive"))
    )
    (net (code "63") (name "Net-(VT1-D)") (class "Default")
      (node (ref "R19") (pin "2") (pinfunction "2_2") (pintype "passive"))
      (node (ref "VT1") (pin "2") (pinfunction "D_2") (pintype "passive"))
    )
    (net (code "64") (name "Net-(VT1-G)") (class "Default")
      (node (ref "R13") (pin "1") (pinfunction "1_1") (pintype "passive"))
      (node (ref "R17") (pin "2") (pinfunction "2_2") (pintype "passive"))
      (node (ref "VT1") (pin "1") (pinfunction "G_1") (pintype "passive"))
    )
    (net (code "65") (name "Net-(VT15-G)") (class "Default")
      (node (ref "R100") (pin "2") (pinfunction "2_2") (pintype "passive"))
      (node (ref "R98") (pin "1") (pinfunction "1_1") (pintype "passive"))
      (node (ref "VT15") (pin "1") (pinfunction "G_1") (pintype "passive"))
    )
    (net (code "66") (name "Net-(VT16-G)") (class "Default")
      (node (ref "R101") (pin "2") (pinfunction "2_2") (pintype "passive"))
      (node (ref "R99") (pin "1") (pinfunction "1_1") (pintype "passive"))
      (node (ref "VT16") (pin "1") (pinfunction "G_1") (pintype "passive"))
    )
    (net (code "67") (name "Net-(VT17-G)") (class "Default")
      (node (ref "R108") (pin "1") (pinfunction "1_1") (pintype "passive"))
      (node (ref "R111") (pin "2") (pinfunction "2_2") (pintype "passive"))
      (node (ref "VT17") (pin "1") (pinfunction "G_1") (pintype "passive"))
    )
    (net (code "68") (name "Net-(VT18-G)") (class "Default")
      (node (ref "R109") (pin "1") (pinfunction "1_1") (pintype "passive"))
      (node (ref "R112") (pin "2") (pinfunction "2_2") (pintype "passive"))
      (node (ref "VT18") (pin "1") (pinfunction "G_1") (pintype "passive"))
    )
    (net (code "69") (name "Net-(VT19-G)") (class "Default")
      (node (ref "R110") (pin "1") (pinfunction "1_1") (pintype "passive"))
      (node (ref "R113") (pin "2") (pinfunction "2_2") (pintype "passive"))
      (node (ref "VT19") (pin "1") (pinfunction "G_1") (pintype "passive"))
    )
    (net (code "70") (name "unconnected-(X6-Pad6)") (class "Default")
      (node (ref "X6") (pin "6") (pinfunction "6_6") (pintype "power_in"))
    )
    (net (code "71") (name "unconnected-(X8-Pad4)") (class "Default")
      (node (ref "X8") (pin "4") (pinfunction "4_4") (pintype "power_in"))
    )
    (net (code "72") (name "unconnected-(X8-Pad5)") (class "Default")
      (node (ref "X8") (pin "5") (pinfunction "5_5") (pintype "power_in"))
    )
  )
)
